# EDU_High-Speed-Design_DDR3.net
KiCad netlist of a schematic drawn in Altium Designer
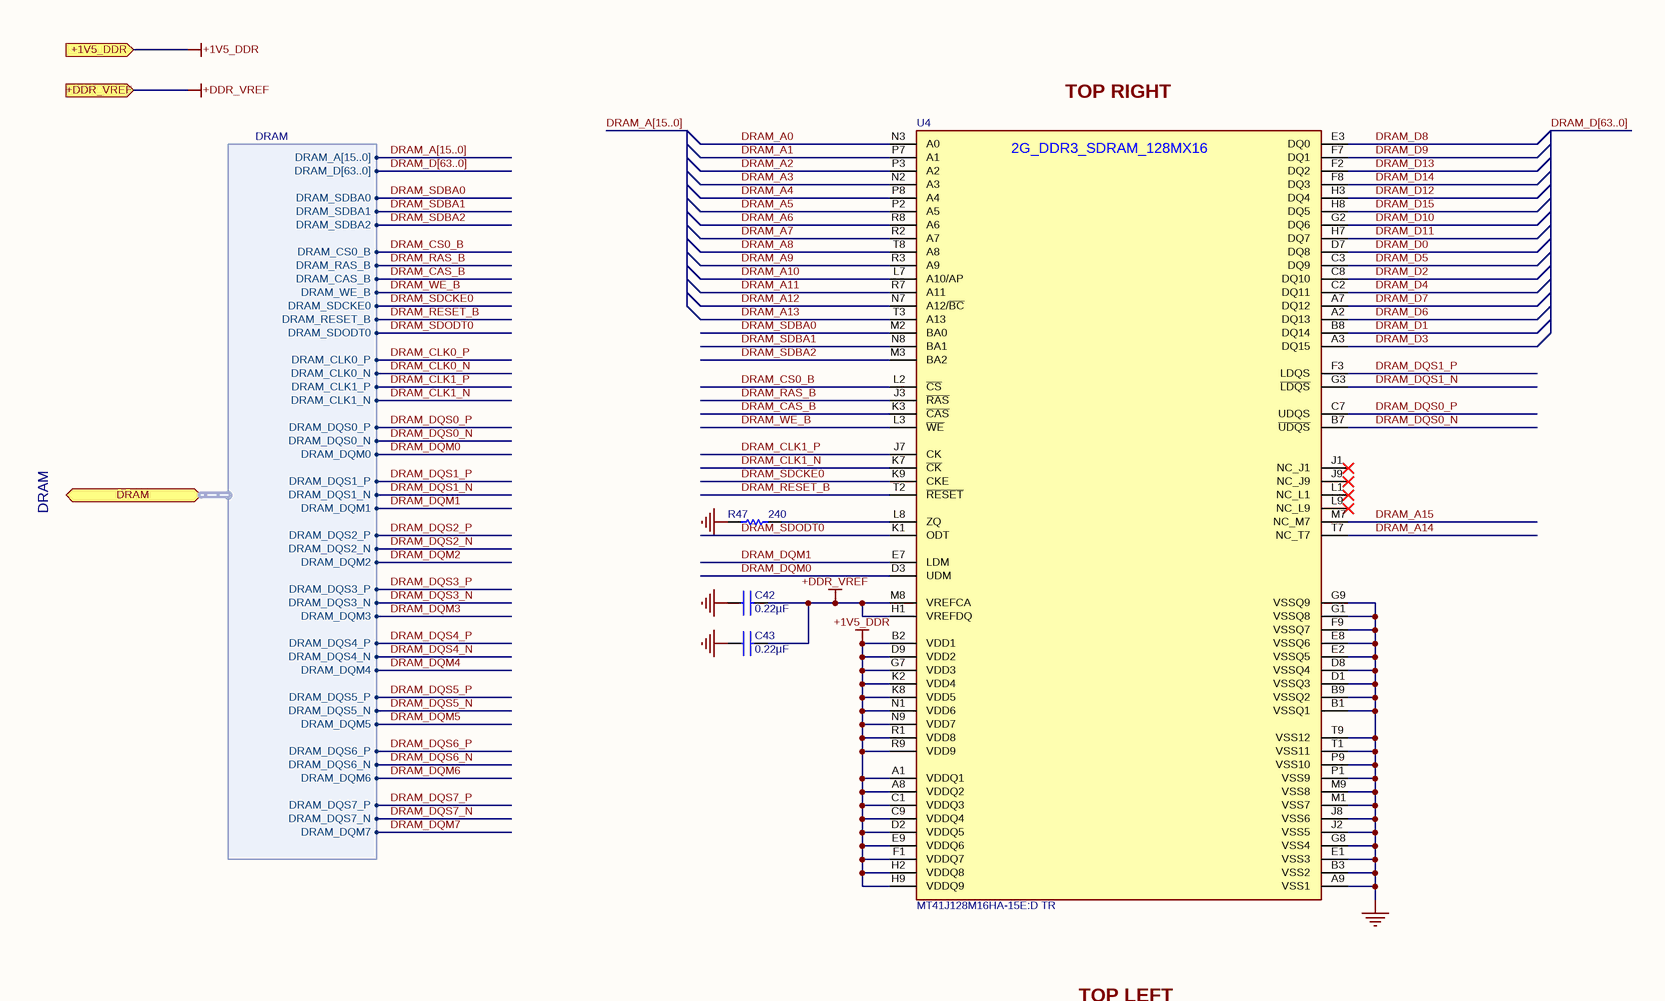
[diagram p0: EDU_High-Speed-Design_DDR3.SchDoc, top left]
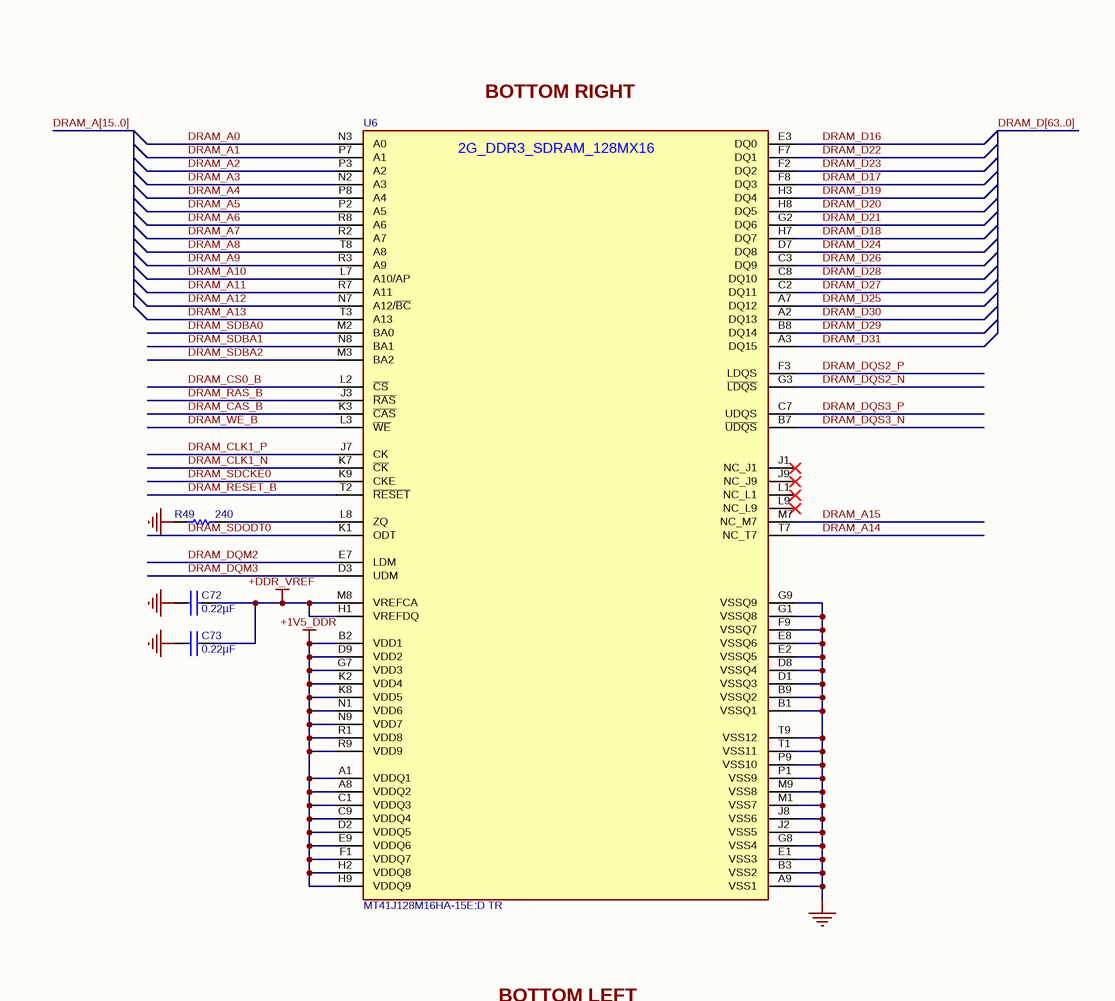
[diagram p1: EDU_High-Speed-Design_DDR3.SchDoc, top right]
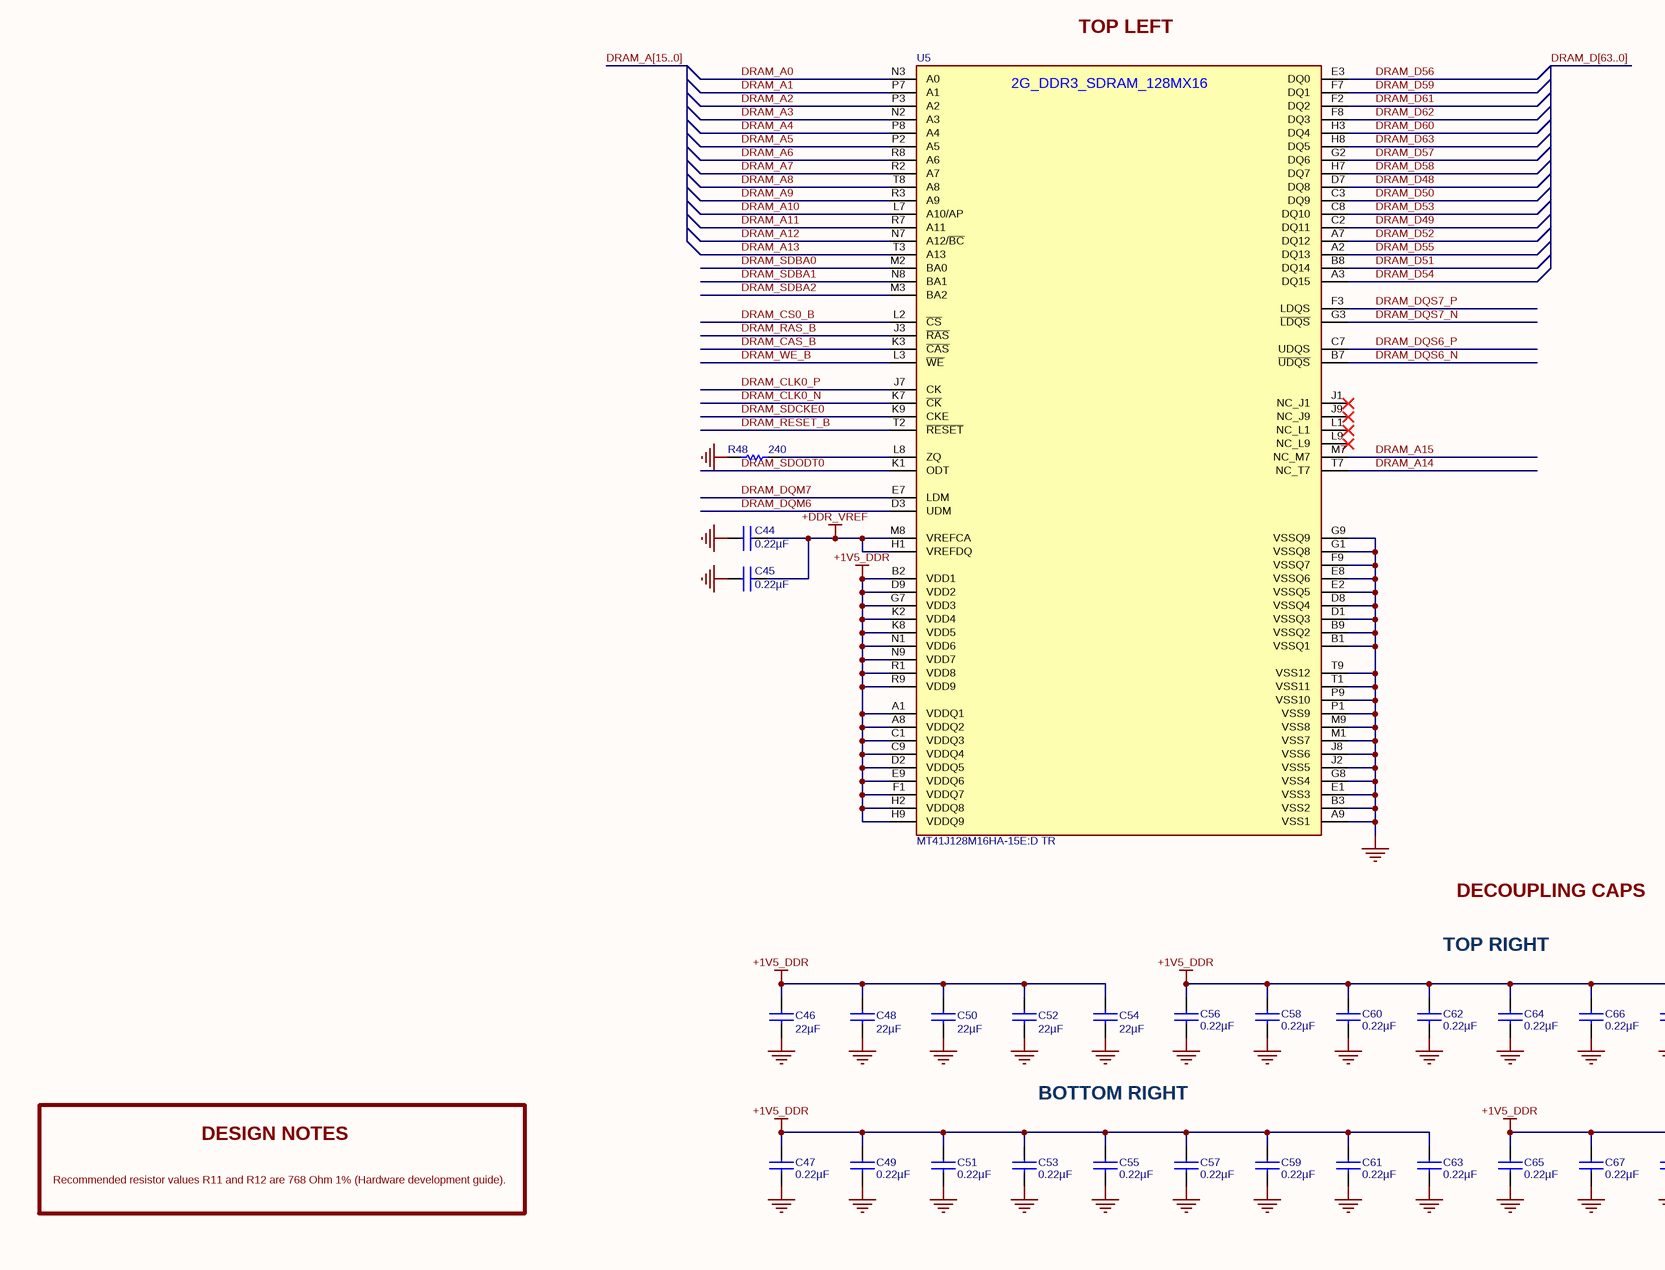
[diagram p2: EDU_High-Speed-Design_DDR3.SchDoc, bottom left]
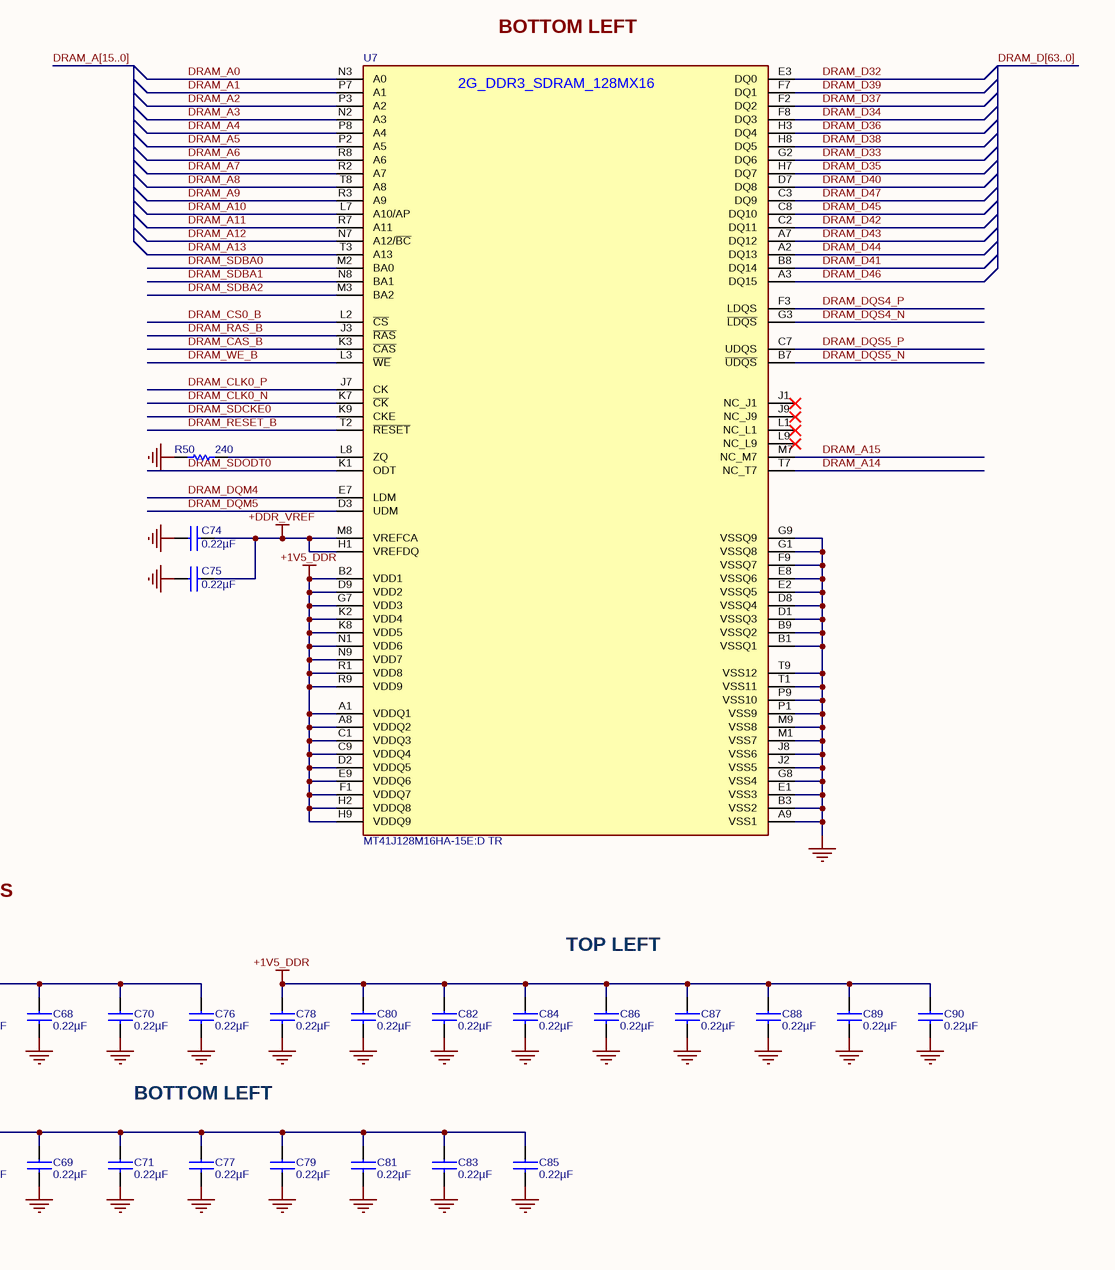
[diagram p3: EDU_High-Speed-Design_DDR3.SchDoc, bottom right]

(export (version "E")
  (design (tool "Eeschema 10.0.6"))
  (components
    (comp (ref "C42")
      (value "0.22µF")
      (footprint "C0402")
      (description "CAP CER .22UF 25V X5R 20% 0402")
      (fields (field (name "VOLTAGE") "25V"))
      (libsource (lib "EDU_High-Speed-Design") (part "C1005X5R1E224M"))
    )
    (comp (ref "C43")
      (value "0.22µF")
      (footprint "C0402")
      (description "CAP CER .22UF 25V X5R 20% 0402")
      (fields (field (name "VOLTAGE") "25V"))
      (libsource (lib "EDU_High-Speed-Design") (part "C1005X5R1E224M"))
    )
    (comp (ref "C44")
      (value "0.22µF")
      (footprint "C0402")
      (description "CAP CER .22UF 25V X5R 20% 0402")
      (fields (field (name "VOLTAGE") "25V"))
      (libsource (lib "EDU_High-Speed-Design") (part "C1005X5R1E224M"))
    )
    (comp (ref "C45")
      (value "0.22µF")
      (footprint "C0402")
      (description "CAP CER .22UF 25V X5R 20% 0402")
      (fields (field (name "VOLTAGE") "25V"))
      (libsource (lib "EDU_High-Speed-Design") (part "C1005X5R1E224M"))
    )
    (comp (ref "C46")
      (value "22µF")
      (footprint "C0603")
      (description "CAP CER 22UF 4V 20% X5R 0603")
      (fields (field (name "VOLTAGE") "4V"))
      (libsource (lib "EDU_High-Speed-Design") (part "GRM188R60G226MEA0L"))
    )
    (comp (ref "C47")
      (value "0.22µF")
      (footprint "C0402")
      (description "CAP CER .22UF 25V X5R 20% 0402")
      (fields (field (name "VOLTAGE") "25V"))
      (libsource (lib "EDU_High-Speed-Design") (part "C1005X5R1E224M"))
    )
    (comp (ref "C48")
      (value "22µF")
      (footprint "C0603")
      (description "CAP CER 22UF 4V 20% X5R 0603")
      (fields (field (name "VOLTAGE") "4V"))
      (libsource (lib "EDU_High-Speed-Design") (part "GRM188R60G226MEA0L"))
    )
    (comp (ref "C49")
      (value "0.22µF")
      (footprint "C0402")
      (description "CAP CER .22UF 25V X5R 20% 0402")
      (fields (field (name "VOLTAGE") "25V"))
      (libsource (lib "EDU_High-Speed-Design") (part "C1005X5R1E224M"))
    )
    (comp (ref "C50")
      (value "22µF")
      (footprint "C0603")
      (description "CAP CER 22UF 4V 20% X5R 0603")
      (fields (field (name "VOLTAGE") "4V"))
      (libsource (lib "EDU_High-Speed-Design") (part "GRM188R60G226MEA0L"))
    )
    (comp (ref "C51")
      (value "0.22µF")
      (footprint "C0402")
      (description "CAP CER .22UF 25V X5R 20% 0402")
      (fields (field (name "VOLTAGE") "25V"))
      (libsource (lib "EDU_High-Speed-Design") (part "C1005X5R1E224M"))
    )
    (comp (ref "C52")
      (value "22µF")
      (footprint "C0603")
      (description "CAP CER 22UF 4V 20% X5R 0603")
      (fields (field (name "VOLTAGE") "4V"))
      (libsource (lib "EDU_High-Speed-Design") (part "GRM188R60G226MEA0L"))
    )
    (comp (ref "C53")
      (value "0.22µF")
      (footprint "C0402")
      (description "CAP CER .22UF 25V X5R 20% 0402")
      (fields (field (name "VOLTAGE") "25V"))
      (libsource (lib "EDU_High-Speed-Design") (part "C1005X5R1E224M"))
    )
    (comp (ref "C54")
      (value "22µF")
      (footprint "C0603")
      (description "CAP CER 22UF 4V 20% X5R 0603")
      (fields (field (name "VOLTAGE") "4V"))
      (libsource (lib "EDU_High-Speed-Design") (part "GRM188R60G226MEA0L"))
    )
    (comp (ref "C55")
      (value "0.22µF")
      (footprint "C0402")
      (description "CAP CER .22UF 25V X5R 20% 0402")
      (fields (field (name "VOLTAGE") "25V"))
      (libsource (lib "EDU_High-Speed-Design") (part "C1005X5R1E224M"))
    )
    (comp (ref "C56")
      (value "0.22µF")
      (footprint "C0402")
      (description "CAP CER .22UF 25V X5R 20% 0402")
      (fields (field (name "VOLTAGE") "25V"))
      (libsource (lib "EDU_High-Speed-Design") (part "C1005X5R1E224M"))
    )
    (comp (ref "C57")
      (value "0.22µF")
      (footprint "C0402")
      (description "CAP CER .22UF 25V X5R 20% 0402")
      (fields (field (name "VOLTAGE") "25V"))
      (libsource (lib "EDU_High-Speed-Design") (part "C1005X5R1E224M"))
    )
    (comp (ref "C58")
      (value "0.22µF")
      (footprint "C0402")
      (description "CAP CER .22UF 25V X5R 20% 0402")
      (fields (field (name "VOLTAGE") "25V"))
      (libsource (lib "EDU_High-Speed-Design") (part "C1005X5R1E224M"))
    )
    (comp (ref "C59")
      (value "0.22µF")
      (footprint "C0402")
      (description "CAP CER .22UF 25V X5R 20% 0402")
      (fields (field (name "VOLTAGE") "25V"))
      (libsource (lib "EDU_High-Speed-Design") (part "C1005X5R1E224M"))
    )
    (comp (ref "C60")
      (value "0.22µF")
      (footprint "C0402")
      (description "CAP CER .22UF 25V X5R 20% 0402")
      (fields (field (name "VOLTAGE") "25V"))
      (libsource (lib "EDU_High-Speed-Design") (part "C1005X5R1E224M"))
    )
    (comp (ref "C61")
      (value "0.22µF")
      (footprint "C0402")
      (description "CAP CER .22UF 25V X5R 20% 0402")
      (fields (field (name "VOLTAGE") "25V"))
      (libsource (lib "EDU_High-Speed-Design") (part "C1005X5R1E224M"))
    )
    (comp (ref "C62")
      (value "0.22µF")
      (footprint "C0402")
      (description "CAP CER .22UF 25V X5R 20% 0402")
      (fields (field (name "VOLTAGE") "25V"))
      (libsource (lib "EDU_High-Speed-Design") (part "C1005X5R1E224M"))
    )
    (comp (ref "C63")
      (value "0.22µF")
      (footprint "C0402")
      (description "CAP CER .22UF 25V X5R 20% 0402")
      (fields (field (name "VOLTAGE") "25V"))
      (libsource (lib "EDU_High-Speed-Design") (part "C1005X5R1E224M"))
    )
    (comp (ref "C64")
      (value "0.22µF")
      (footprint "C0402")
      (description "CAP CER .22UF 25V X5R 20% 0402")
      (fields (field (name "VOLTAGE") "25V"))
      (libsource (lib "EDU_High-Speed-Design") (part "C1005X5R1E224M"))
    )
    (comp (ref "C65")
      (value "0.22µF")
      (footprint "C0402")
      (description "CAP CER .22UF 25V X5R 20% 0402")
      (fields (field (name "VOLTAGE") "25V"))
      (libsource (lib "EDU_High-Speed-Design") (part "C1005X5R1E224M"))
    )
    (comp (ref "C66")
      (value "0.22µF")
      (footprint "C0402")
      (description "CAP CER .22UF 25V X5R 20% 0402")
      (fields (field (name "VOLTAGE") "25V"))
      (libsource (lib "EDU_High-Speed-Design") (part "C1005X5R1E224M"))
    )
    (comp (ref "C67")
      (value "0.22µF")
      (footprint "C0402")
      (description "CAP CER .22UF 25V X5R 20% 0402")
      (fields (field (name "VOLTAGE") "25V"))
      (libsource (lib "EDU_High-Speed-Design") (part "C1005X5R1E224M"))
    )
    (comp (ref "C68")
      (value "0.22µF")
      (footprint "C0402")
      (description "CAP CER .22UF 25V X5R 20% 0402")
      (fields (field (name "VOLTAGE") "25V"))
      (libsource (lib "EDU_High-Speed-Design") (part "C1005X5R1E224M"))
    )
    (comp (ref "C69")
      (value "0.22µF")
      (footprint "C0402")
      (description "CAP CER .22UF 25V X5R 20% 0402")
      (fields (field (name "VOLTAGE") "25V"))
      (libsource (lib "EDU_High-Speed-Design") (part "C1005X5R1E224M"))
    )
    (comp (ref "C70")
      (value "0.22µF")
      (footprint "C0402")
      (description "CAP CER .22UF 25V X5R 20% 0402")
      (fields (field (name "VOLTAGE") "25V"))
      (libsource (lib "EDU_High-Speed-Design") (part "C1005X5R1E224M"))
    )
    (comp (ref "C71")
      (value "0.22µF")
      (footprint "C0402")
      (description "CAP CER .22UF 25V X5R 20% 0402")
      (fields (field (name "VOLTAGE") "25V"))
      (libsource (lib "EDU_High-Speed-Design") (part "C1005X5R1E224M"))
    )
    (comp (ref "C72")
      (value "0.22µF")
      (footprint "C0402")
      (description "CAP CER .22UF 25V X5R 20% 0402")
      (fields (field (name "VOLTAGE") "25V"))
      (libsource (lib "EDU_High-Speed-Design") (part "C1005X5R1E224M"))
    )
    (comp (ref "C73")
      (value "0.22µF")
      (footprint "C0402")
      (description "CAP CER .22UF 25V X5R 20% 0402")
      (fields (field (name "VOLTAGE") "25V"))
      (libsource (lib "EDU_High-Speed-Design") (part "C1005X5R1E224M"))
    )
    (comp (ref "C74")
      (value "0.22µF")
      (footprint "C0402")
      (description "CAP CER .22UF 25V X5R 20% 0402")
      (fields (field (name "VOLTAGE") "25V"))
      (libsource (lib "EDU_High-Speed-Design") (part "C1005X5R1E224M"))
    )
    (comp (ref "C75")
      (value "0.22µF")
      (footprint "C0402")
      (description "CAP CER .22UF 25V X5R 20% 0402")
      (fields (field (name "VOLTAGE") "25V"))
      (libsource (lib "EDU_High-Speed-Design") (part "C1005X5R1E224M"))
    )
    (comp (ref "C76")
      (value "0.22µF")
      (footprint "C0402")
      (description "CAP CER .22UF 25V X5R 20% 0402")
      (fields (field (name "VOLTAGE") "25V"))
      (libsource (lib "EDU_High-Speed-Design") (part "C1005X5R1E224M"))
    )
    (comp (ref "C77")
      (value "0.22µF")
      (footprint "C0402")
      (description "CAP CER .22UF 25V X5R 20% 0402")
      (fields (field (name "VOLTAGE") "25V"))
      (libsource (lib "EDU_High-Speed-Design") (part "C1005X5R1E224M"))
    )
    (comp (ref "C78")
      (value "0.22µF")
      (footprint "C0402")
      (description "CAP CER .22UF 25V X5R 20% 0402")
      (fields (field (name "VOLTAGE") "25V"))
      (libsource (lib "EDU_High-Speed-Design") (part "C1005X5R1E224M"))
    )
    (comp (ref "C79")
      (value "0.22µF")
      (footprint "C0402")
      (description "CAP CER .22UF 25V X5R 20% 0402")
      (fields (field (name "VOLTAGE") "25V"))
      (libsource (lib "EDU_High-Speed-Design") (part "C1005X5R1E224M"))
    )
    (comp (ref "C80")
      (value "0.22µF")
      (footprint "C0402")
      (description "CAP CER .22UF 25V X5R 20% 0402")
      (fields (field (name "VOLTAGE") "25V"))
      (libsource (lib "EDU_High-Speed-Design") (part "C1005X5R1E224M"))
    )
    (comp (ref "C81")
      (value "0.22µF")
      (footprint "C0402")
      (description "CAP CER .22UF 25V X5R 20% 0402")
      (fields (field (name "VOLTAGE") "25V"))
      (libsource (lib "EDU_High-Speed-Design") (part "C1005X5R1E224M"))
    )
    (comp (ref "C82")
      (value "0.22µF")
      (footprint "C0402")
      (description "CAP CER .22UF 25V X5R 20% 0402")
      (fields (field (name "VOLTAGE") "25V"))
      (libsource (lib "EDU_High-Speed-Design") (part "C1005X5R1E224M"))
    )
    (comp (ref "C83")
      (value "0.22µF")
      (footprint "C0402")
      (description "CAP CER .22UF 25V X5R 20% 0402")
      (fields (field (name "VOLTAGE") "25V"))
      (libsource (lib "EDU_High-Speed-Design") (part "C1005X5R1E224M"))
    )
    (comp (ref "C84")
      (value "0.22µF")
      (footprint "C0402")
      (description "CAP CER .22UF 25V X5R 20% 0402")
      (fields (field (name "VOLTAGE") "25V"))
      (libsource (lib "EDU_High-Speed-Design") (part "C1005X5R1E224M"))
    )
    (comp (ref "C85")
      (value "0.22µF")
      (footprint "C0402")
      (description "CAP CER .22UF 25V X5R 20% 0402")
      (fields (field (name "VOLTAGE") "25V"))
      (libsource (lib "EDU_High-Speed-Design") (part "C1005X5R1E224M"))
    )
    (comp (ref "C86")
      (value "0.22µF")
      (footprint "C0402")
      (description "CAP CER .22UF 25V X5R 20% 0402")
      (fields (field (name "VOLTAGE") "25V"))
      (libsource (lib "EDU_High-Speed-Design") (part "C1005X5R1E224M"))
    )
    (comp (ref "C87")
      (value "0.22µF")
      (footprint "C0402")
      (description "CAP CER .22UF 25V X5R 20% 0402")
      (fields (field (name "VOLTAGE") "25V"))
      (libsource (lib "EDU_High-Speed-Design") (part "C1005X5R1E224M"))
    )
    (comp (ref "C88")
      (value "0.22µF")
      (footprint "C0402")
      (description "CAP CER .22UF 25V X5R 20% 0402")
      (fields (field (name "VOLTAGE") "25V"))
      (libsource (lib "EDU_High-Speed-Design") (part "C1005X5R1E224M"))
    )
    (comp (ref "C89")
      (value "0.22µF")
      (footprint "C0402")
      (description "CAP CER .22UF 25V X5R 20% 0402")
      (fields (field (name "VOLTAGE") "25V"))
      (libsource (lib "EDU_High-Speed-Design") (part "C1005X5R1E224M"))
    )
    (comp (ref "C90")
      (value "0.22µF")
      (footprint "C0402")
      (description "CAP CER .22UF 25V X5R 20% 0402")
      (fields (field (name "VOLTAGE") "25V"))
      (libsource (lib "EDU_High-Speed-Design") (part "C1005X5R1E224M"))
    )
    (comp (ref "R47")
      (value "240")
      (footprint "R0402")
      (description "RES TF 240 OHM 1% 0.0625W 0402")
      (libsource (lib "EDU_High-Speed-Design") (part "RMCF0402FT240R"))
    )
    (comp (ref "R48")
      (value "240")
      (footprint "R0402")
      (description "RES TF 240 OHM 1% 0.0625W 0402")
      (libsource (lib "EDU_High-Speed-Design") (part "RMCF0402FT240R"))
    )
    (comp (ref "R49")
      (value "240")
      (footprint "R0402")
      (description "RES TF 240 OHM 1% 0.0625W 0402")
      (libsource (lib "EDU_High-Speed-Design") (part "RMCF0402FT240R"))
    )
    (comp (ref "R50")
      (value "240")
      (footprint "R0402")
      (description "RES TF 240 OHM 1% 0.0625W 0402")
      (libsource (lib "EDU_High-Speed-Design") (part "RMCF0402FT240R"))
    )
    (comp (ref "U4")
      (value "MT41J128M16HA-15E:D TR")
      (footprint "MT41J128M16HA-15E:D TR")
      (description "IC DDR3 SDRAM 2GBIT 667MHZ 96BGA")
      (libsource (lib "EDU_High-Speed-Design") (part "MT41J128M16HA-15E{colon}D TR"))
    )
    (comp (ref "U5")
      (value "MT41J128M16HA-15E:D TR")
      (footprint "MT41J128M16HA-15E:D TR")
      (description "IC DDR3 SDRAM 2GBIT 667MHZ 96BGA")
      (libsource (lib "EDU_High-Speed-Design") (part "MT41J128M16HA-15E{colon}D TR"))
    )
    (comp (ref "U6")
      (value "MT41J128M16HA-15E:D TR")
      (footprint "MT41J128M16HA-15E:D TR")
      (description "IC DDR3 SDRAM 2GBIT 667MHZ 96BGA")
      (libsource (lib "EDU_High-Speed-Design") (part "MT41J128M16HA-15E{colon}D TR"))
    )
    (comp (ref "U7")
      (value "MT41J128M16HA-15E:D TR")
      (footprint "MT41J128M16HA-15E:D TR")
      (description "IC DDR3 SDRAM 2GBIT 667MHZ 96BGA")
      (libsource (lib "EDU_High-Speed-Design") (part "MT41J128M16HA-15E{colon}D TR"))
    )
  )
  (nets
    (net (code "2") (name "+1V5_DDR") (class "Default")
      (node (ref "C46") (pin "1") (pinfunction "1_1") (pintype "passive"))
      (node (ref "C47") (pin "1") (pinfunction "1_1") (pintype "passive"))
      (node (ref "C48") (pin "1") (pinfunction "1_1") (pintype "passive"))
      (node (ref "C49") (pin "1") (pinfunction "1_1") (pintype "passive"))
      (node (ref "C50") (pin "1") (pinfunction "1_1") (pintype "passive"))
      (node (ref "C51") (pin "1") (pinfunction "1_1") (pintype "passive"))
      (node (ref "C52") (pin "1") (pinfunction "1_1") (pintype "passive"))
      (node (ref "C53") (pin "1") (pinfunction "1_1") (pintype "passive"))
      (node (ref "C54") (pin "1") (pinfunction "1_1") (pintype "passive"))
      (node (ref "C55") (pin "1") (pinfunction "1_1") (pintype "passive"))
      (node (ref "C56") (pin "1") (pinfunction "1_1") (pintype "passive"))
      (node (ref "C57") (pin "1") (pinfunction "1_1") (pintype "passive"))
      (node (ref "C58") (pin "1") (pinfunction "1_1") (pintype "passive"))
      (node (ref "C59") (pin "1") (pinfunction "1_1") (pintype "passive"))
      (node (ref "C60") (pin "1") (pinfunction "1_1") (pintype "passive"))
      (node (ref "C61") (pin "1") (pinfunction "1_1") (pintype "passive"))
      (node (ref "C62") (pin "1") (pinfunction "1_1") (pintype "passive"))
      (node (ref "C63") (pin "1") (pinfunction "1_1") (pintype "passive"))
      (node (ref "C64") (pin "1") (pinfunction "1_1") (pintype "passive"))
      (node (ref "C65") (pin "1") (pinfunction "1_1") (pintype "passive"))
      (node (ref "C66") (pin "1") (pinfunction "1_1") (pintype "passive"))
      (node (ref "C67") (pin "1") (pinfunction "1_1") (pintype "passive"))
      (node (ref "C68") (pin "1") (pinfunction "1_1") (pintype "passive"))
      (node (ref "C69") (pin "1") (pinfunction "1_1") (pintype "passive"))
      (node (ref "C70") (pin "1") (pinfunction "1_1") (pintype "passive"))
      (node (ref "C71") (pin "1") (pinfunction "1_1") (pintype "passive"))
      (node (ref "C76") (pin "1") (pinfunction "1_1") (pintype "passive"))
      (node (ref "C77") (pin "1") (pinfunction "1_1") (pintype "passive"))
      (node (ref "C78") (pin "1") (pinfunction "1_1") (pintype "passive"))
      (node (ref "C79") (pin "1") (pinfunction "1_1") (pintype "passive"))
      (node (ref "C80") (pin "1") (pinfunction "1_1") (pintype "passive"))
      (node (ref "C81") (pin "1") (pinfunction "1_1") (pintype "passive"))
      (node (ref "C82") (pin "1") (pinfunction "1_1") (pintype "passive"))
      (node (ref "C83") (pin "1") (pinfunction "1_1") (pintype "passive"))
      (node (ref "C84") (pin "1") (pinfunction "1_1") (pintype "passive"))
      (node (ref "C85") (pin "1") (pinfunction "1_1") (pintype "passive"))
      (node (ref "C86") (pin "1") (pinfunction "1_1") (pintype "passive"))
      (node (ref "C87") (pin "1") (pinfunction "1_1") (pintype "passive"))
      (node (ref "C88") (pin "1") (pinfunction "1_1") (pintype "passive"))
      (node (ref "C89") (pin "1") (pinfunction "1_1") (pintype "passive"))
      (node (ref "C90") (pin "1") (pinfunction "1_1") (pintype "passive"))
      (node (ref "U4") (pin "A1") (pinfunction "VDDQ1_A1") (pintype "passive"))
      (node (ref "U4") (pin "A8") (pinfunction "VDDQ2_A8") (pintype "passive"))
      (node (ref "U4") (pin "B2") (pinfunction "VDD1_B2") (pintype "passive"))
      (node (ref "U4") (pin "C1") (pinfunction "VDDQ3_C1") (pintype "passive"))
      (node (ref "U4") (pin "C9") (pinfunction "VDDQ4_C9") (pintype "passive"))
      (node (ref "U4") (pin "D2") (pinfunction "VDDQ5_D2") (pintype "passive"))
      (node (ref "U4") (pin "D9") (pinfunction "VDD2_D9") (pintype "passive"))
      (node (ref "U4") (pin "E9") (pinfunction "VDDQ6_E9") (pintype "passive"))
      (node (ref "U4") (pin "F1") (pinfunction "VDDQ7_F1") (pintype "passive"))
      (node (ref "U4") (pin "G7") (pinfunction "VDD3_G7") (pintype "passive"))
      (node (ref "U4") (pin "H2") (pinfunction "VDDQ8_H2") (pintype "passive"))
      (node (ref "U4") (pin "H9") (pinfunction "VDDQ9_H9") (pintype "passive"))
      (node (ref "U4") (pin "K2") (pinfunction "VDD4_K2") (pintype "passive"))
      (node (ref "U4") (pin "K8") (pinfunction "VDD5_K8") (pintype "passive"))
      (node (ref "U4") (pin "N1") (pinfunction "VDD6_N1") (pintype "passive"))
      (node (ref "U4") (pin "N9") (pinfunction "VDD7_N9") (pintype "passive"))
      (node (ref "U4") (pin "R1") (pinfunction "VDD8_R1") (pintype "passive"))
      (node (ref "U4") (pin "R9") (pinfunction "VDD9_R9") (pintype "passive"))
      (node (ref "U5") (pin "A1") (pinfunction "VDDQ1_A1") (pintype "passive"))
      (node (ref "U5") (pin "A8") (pinfunction "VDDQ2_A8") (pintype "passive"))
      (node (ref "U5") (pin "B2") (pinfunction "VDD1_B2") (pintype "passive"))
      (node (ref "U5") (pin "C1") (pinfunction "VDDQ3_C1") (pintype "passive"))
      (node (ref "U5") (pin "C9") (pinfunction "VDDQ4_C9") (pintype "passive"))
      (node (ref "U5") (pin "D2") (pinfunction "VDDQ5_D2") (pintype "passive"))
      (node (ref "U5") (pin "D9") (pinfunction "VDD2_D9") (pintype "passive"))
      (node (ref "U5") (pin "E9") (pinfunction "VDDQ6_E9") (pintype "passive"))
      (node (ref "U5") (pin "F1") (pinfunction "VDDQ7_F1") (pintype "passive"))
      (node (ref "U5") (pin "G7") (pinfunction "VDD3_G7") (pintype "passive"))
      (node (ref "U5") (pin "H2") (pinfunction "VDDQ8_H2") (pintype "passive"))
      (node (ref "U5") (pin "H9") (pinfunction "VDDQ9_H9") (pintype "passive"))
      (node (ref "U5") (pin "K2") (pinfunction "VDD4_K2") (pintype "passive"))
      (node (ref "U5") (pin "K8") (pinfunction "VDD5_K8") (pintype "passive"))
      (node (ref "U5") (pin "N1") (pinfunction "VDD6_N1") (pintype "passive"))
      (node (ref "U5") (pin "N9") (pinfunction "VDD7_N9") (pintype "passive"))
      (node (ref "U5") (pin "R1") (pinfunction "VDD8_R1") (pintype "passive"))
      (node (ref "U5") (pin "R9") (pinfunction "VDD9_R9") (pintype "passive"))
      (node (ref "U6") (pin "A1") (pinfunction "VDDQ1_A1") (pintype "passive"))
      (node (ref "U6") (pin "A8") (pinfunction "VDDQ2_A8") (pintype "passive"))
      (node (ref "U6") (pin "B2") (pinfunction "VDD1_B2") (pintype "passive"))
      (node (ref "U6") (pin "C1") (pinfunction "VDDQ3_C1") (pintype "passive"))
      (node (ref "U6") (pin "C9") (pinfunction "VDDQ4_C9") (pintype "passive"))
      (node (ref "U6") (pin "D2") (pinfunction "VDDQ5_D2") (pintype "passive"))
      (node (ref "U6") (pin "D9") (pinfunction "VDD2_D9") (pintype "passive"))
      (node (ref "U6") (pin "E9") (pinfunction "VDDQ6_E9") (pintype "passive"))
      (node (ref "U6") (pin "F1") (pinfunction "VDDQ7_F1") (pintype "passive"))
      (node (ref "U6") (pin "G7") (pinfunction "VDD3_G7") (pintype "passive"))
      (node (ref "U6") (pin "H2") (pinfunction "VDDQ8_H2") (pintype "passive"))
      (node (ref "U6") (pin "H9") (pinfunction "VDDQ9_H9") (pintype "passive"))
      (node (ref "U6") (pin "K2") (pinfunction "VDD4_K2") (pintype "passive"))
      (node (ref "U6") (pin "K8") (pinfunction "VDD5_K8") (pintype "passive"))
      (node (ref "U6") (pin "N1") (pinfunction "VDD6_N1") (pintype "passive"))
      (node (ref "U6") (pin "N9") (pinfunction "VDD7_N9") (pintype "passive"))
      (node (ref "U6") (pin "R1") (pinfunction "VDD8_R1") (pintype "passive"))
      (node (ref "U6") (pin "R9") (pinfunction "VDD9_R9") (pintype "passive"))
      (node (ref "U7") (pin "A1") (pinfunction "VDDQ1_A1") (pintype "passive"))
      (node (ref "U7") (pin "A8") (pinfunction "VDDQ2_A8") (pintype "passive"))
      (node (ref "U7") (pin "B2") (pinfunction "VDD1_B2") (pintype "passive"))
      (node (ref "U7") (pin "C1") (pinfunction "VDDQ3_C1") (pintype "passive"))
      (node (ref "U7") (pin "C9") (pinfunction "VDDQ4_C9") (pintype "passive"))
      (node (ref "U7") (pin "D2") (pinfunction "VDDQ5_D2") (pintype "passive"))
      (node (ref "U7") (pin "D9") (pinfunction "VDD2_D9") (pintype "passive"))
      (node (ref "U7") (pin "E9") (pinfunction "VDDQ6_E9") (pintype "passive"))
      (node (ref "U7") (pin "F1") (pinfunction "VDDQ7_F1") (pintype "passive"))
      (node (ref "U7") (pin "G7") (pinfunction "VDD3_G7") (pintype "passive"))
      (node (ref "U7") (pin "H2") (pinfunction "VDDQ8_H2") (pintype "passive"))
      (node (ref "U7") (pin "H9") (pinfunction "VDDQ9_H9") (pintype "passive"))
      (node (ref "U7") (pin "K2") (pinfunction "VDD4_K2") (pintype "passive"))
      (node (ref "U7") (pin "K8") (pinfunction "VDD5_K8") (pintype "passive"))
      (node (ref "U7") (pin "N1") (pinfunction "VDD6_N1") (pintype "passive"))
      (node (ref "U7") (pin "N9") (pinfunction "VDD7_N9") (pintype "passive"))
      (node (ref "U7") (pin "R1") (pinfunction "VDD8_R1") (pintype "passive"))
      (node (ref "U7") (pin "R9") (pinfunction "VDD9_R9") (pintype "passive"))
    )
    (net (code "3") (name "+DDR_VREF") (class "Default")
      (node (ref "C42") (pin "2") (pinfunction "2_2") (pintype "passive"))
      (node (ref "C43") (pin "2") (pinfunction "2_2") (pintype "passive"))
      (node (ref "C44") (pin "2") (pinfunction "2_2") (pintype "passive"))
      (node (ref "C45") (pin "2") (pinfunction "2_2") (pintype "passive"))
      (node (ref "C72") (pin "2") (pinfunction "2_2") (pintype "passive"))
      (node (ref "C73") (pin "2") (pinfunction "2_2") (pintype "passive"))
      (node (ref "C74") (pin "2") (pinfunction "2_2") (pintype "passive"))
      (node (ref "C75") (pin "2") (pinfunction "2_2") (pintype "passive"))
      (node (ref "U4") (pin "H1") (pinfunction "VREFDQ_H1") (pintype "passive"))
      (node (ref "U4") (pin "M8") (pinfunction "VREFCA_M8") (pintype "passive"))
      (node (ref "U5") (pin "H1") (pinfunction "VREFDQ_H1") (pintype "passive"))
      (node (ref "U5") (pin "M8") (pinfunction "VREFCA_M8") (pintype "passive"))
      (node (ref "U6") (pin "H1") (pinfunction "VREFDQ_H1") (pintype "passive"))
      (node (ref "U6") (pin "M8") (pinfunction "VREFCA_M8") (pintype "passive"))
      (node (ref "U7") (pin "H1") (pinfunction "VREFDQ_H1") (pintype "passive"))
      (node (ref "U7") (pin "M8") (pinfunction "VREFCA_M8") (pintype "passive"))
    )
    (net (code "4") (name "/DRAM_A0") (class "Default")
      (node (ref "U4") (pin "N3") (pinfunction "A0_N3") (pintype "passive"))
      (node (ref "U5") (pin "N3") (pinfunction "A0_N3") (pintype "passive"))
      (node (ref "U6") (pin "N3") (pinfunction "A0_N3") (pintype "passive"))
      (node (ref "U7") (pin "N3") (pinfunction "A0_N3") (pintype "passive"))
    )
    (net (code "5") (name "/DRAM_A1") (class "Default")
      (node (ref "U4") (pin "P7") (pinfunction "A1_P7") (pintype "passive"))
      (node (ref "U5") (pin "P7") (pinfunction "A1_P7") (pintype "passive"))
      (node (ref "U6") (pin "P7") (pinfunction "A1_P7") (pintype "passive"))
      (node (ref "U7") (pin "P7") (pinfunction "A1_P7") (pintype "passive"))
    )
    (net (code "6") (name "/DRAM_A2") (class "Default")
      (node (ref "U4") (pin "P3") (pinfunction "A2_P3") (pintype "passive"))
      (node (ref "U5") (pin "P3") (pinfunction "A2_P3") (pintype "passive"))
      (node (ref "U6") (pin "P3") (pinfunction "A2_P3") (pintype "passive"))
      (node (ref "U7") (pin "P3") (pinfunction "A2_P3") (pintype "passive"))
    )
    (net (code "7") (name "/DRAM_A3") (class "Default")
      (node (ref "U4") (pin "N2") (pinfunction "A3_N2") (pintype "passive"))
      (node (ref "U5") (pin "N2") (pinfunction "A3_N2") (pintype "passive"))
      (node (ref "U6") (pin "N2") (pinfunction "A3_N2") (pintype "passive"))
      (node (ref "U7") (pin "N2") (pinfunction "A3_N2") (pintype "passive"))
    )
    (net (code "8") (name "/DRAM_A4") (class "Default")
      (node (ref "U4") (pin "P8") (pinfunction "A4_P8") (pintype "passive"))
      (node (ref "U5") (pin "P8") (pinfunction "A4_P8") (pintype "passive"))
      (node (ref "U6") (pin "P8") (pinfunction "A4_P8") (pintype "passive"))
      (node (ref "U7") (pin "P8") (pinfunction "A4_P8") (pintype "passive"))
    )
    (net (code "9") (name "/DRAM_A5") (class "Default")
      (node (ref "U4") (pin "P2") (pinfunction "A5_P2") (pintype "passive"))
      (node (ref "U5") (pin "P2") (pinfunction "A5_P2") (pintype "passive"))
      (node (ref "U6") (pin "P2") (pinfunction "A5_P2") (pintype "passive"))
      (node (ref "U7") (pin "P2") (pinfunction "A5_P2") (pintype "passive"))
    )
    (net (code "10") (name "/DRAM_A6") (class "Default")
      (node (ref "U4") (pin "R8") (pinfunction "A6_R8") (pintype "passive"))
      (node (ref "U5") (pin "R8") (pinfunction "A6_R8") (pintype "passive"))
      (node (ref "U6") (pin "R8") (pinfunction "A6_R8") (pintype "passive"))
      (node (ref "U7") (pin "R8") (pinfunction "A6_R8") (pintype "passive"))
    )
    (net (code "11") (name "/DRAM_A7") (class "Default")
      (node (ref "U4") (pin "R2") (pinfunction "A7_R2") (pintype "passive"))
      (node (ref "U5") (pin "R2") (pinfunction "A7_R2") (pintype "passive"))
      (node (ref "U6") (pin "R2") (pinfunction "A7_R2") (pintype "passive"))
      (node (ref "U7") (pin "R2") (pinfunction "A7_R2") (pintype "passive"))
    )
    (net (code "12") (name "/DRAM_A8") (class "Default")
      (node (ref "U4") (pin "T8") (pinfunction "A8_T8") (pintype "passive"))
      (node (ref "U5") (pin "T8") (pinfunction "A8_T8") (pintype "passive"))
      (node (ref "U6") (pin "T8") (pinfunction "A8_T8") (pintype "passive"))
      (node (ref "U7") (pin "T8") (pinfunction "A8_T8") (pintype "passive"))
    )
    (net (code "13") (name "/DRAM_A9") (class "Default")
      (node (ref "U4") (pin "R3") (pinfunction "A9_R3") (pintype "passive"))
      (node (ref "U5") (pin "R3") (pinfunction "A9_R3") (pintype "passive"))
      (node (ref "U6") (pin "R3") (pinfunction "A9_R3") (pintype "passive"))
      (node (ref "U7") (pin "R3") (pinfunction "A9_R3") (pintype "passive"))
    )
    (net (code "14") (name "/DRAM_A10") (class "Default")
      (node (ref "U4") (pin "L7") (pinfunction "A10/AP_L7") (pintype "passive"))
      (node (ref "U5") (pin "L7") (pinfunction "A10/AP_L7") (pintype "passive"))
      (node (ref "U6") (pin "L7") (pinfunction "A10/AP_L7") (pintype "passive"))
      (node (ref "U7") (pin "L7") (pinfunction "A10/AP_L7") (pintype "passive"))
    )
    (net (code "15") (name "/DRAM_A11") (class "Default")
      (node (ref "U4") (pin "R7") (pinfunction "A11_R7") (pintype "passive"))
      (node (ref "U5") (pin "R7") (pinfunction "A11_R7") (pintype "passive"))
      (node (ref "U6") (pin "R7") (pinfunction "A11_R7") (pintype "passive"))
      (node (ref "U7") (pin "R7") (pinfunction "A11_R7") (pintype "passive"))
    )
    (net (code "16") (name "/DRAM_A12") (class "Default")
      (node (ref "U4") (pin "N7") (pinfunction "A12/~{BC}_N7") (pintype "passive"))
      (node (ref "U5") (pin "N7") (pinfunction "A12/~{BC}_N7") (pintype "passive"))
      (node (ref "U6") (pin "N7") (pinfunction "A12/~{BC}_N7") (pintype "passive"))
      (node (ref "U7") (pin "N7") (pinfunction "A12/~{BC}_N7") (pintype "passive"))
    )
    (net (code "17") (name "/DRAM_A13") (class "Default")
      (node (ref "U4") (pin "T3") (pinfunction "A13_T3") (pintype "passive"))
      (node (ref "U5") (pin "T3") (pinfunction "A13_T3") (pintype "passive"))
      (node (ref "U6") (pin "T3") (pinfunction "A13_T3") (pintype "passive"))
      (node (ref "U7") (pin "T3") (pinfunction "A13_T3") (pintype "passive"))
    )
    (net (code "18") (name "/DRAM_A14") (class "Default")
      (node (ref "U4") (pin "T7") (pinfunction "NC_T7_T7") (pintype "passive"))
      (node (ref "U5") (pin "T7") (pinfunction "NC_T7_T7") (pintype "passive"))
      (node (ref "U6") (pin "T7") (pinfunction "NC_T7_T7") (pintype "passive"))
      (node (ref "U7") (pin "T7") (pinfunction "NC_T7_T7") (pintype "passive"))
    )
    (net (code "19") (name "/DRAM_A15") (class "Default")
      (node (ref "U4") (pin "M7") (pinfunction "NC_M7_M7") (pintype "passive"))
      (node (ref "U5") (pin "M7") (pinfunction "NC_M7_M7") (pintype "passive"))
      (node (ref "U6") (pin "M7") (pinfunction "NC_M7_M7") (pintype "passive"))
      (node (ref "U7") (pin "M7") (pinfunction "NC_M7_M7") (pintype "passive"))
    )
    (net (code "21") (name "/DRAM_CAS_B") (class "Default")
      (node (ref "U4") (pin "K3") (pinfunction "~{CAS}_K3") (pintype "passive"))
      (node (ref "U5") (pin "K3") (pinfunction "~{CAS}_K3") (pintype "passive"))
      (node (ref "U6") (pin "K3") (pinfunction "~{CAS}_K3") (pintype "passive"))
      (node (ref "U7") (pin "K3") (pinfunction "~{CAS}_K3") (pintype "passive"))
    )
    (net (code "22") (name "/DRAM_CLK0_N") (class "Default")
      (node (ref "U5") (pin "K7") (pinfunction "~{CK}_K7") (pintype "passive"))
      (node (ref "U7") (pin "K7") (pinfunction "~{CK}_K7") (pintype "passive"))
    )
    (net (code "23") (name "/DRAM_CLK0_P") (class "Default")
      (node (ref "U5") (pin "J7") (pinfunction "CK_J7") (pintype "passive"))
      (node (ref "U7") (pin "J7") (pinfunction "CK_J7") (pintype "passive"))
    )
    (net (code "24") (name "/DRAM_CLK1_N") (class "Default")
      (node (ref "U4") (pin "K7") (pinfunction "~{CK}_K7") (pintype "passive"))
      (node (ref "U6") (pin "K7") (pinfunction "~{CK}_K7") (pintype "passive"))
    )
    (net (code "25") (name "/DRAM_CLK1_P") (class "Default")
      (node (ref "U4") (pin "J7") (pinfunction "CK_J7") (pintype "passive"))
      (node (ref "U6") (pin "J7") (pinfunction "CK_J7") (pintype "passive"))
    )
    (net (code "26") (name "/DRAM_CS0_B") (class "Default")
      (node (ref "U4") (pin "L2") (pinfunction "~{CS}_L2") (pintype "passive"))
      (node (ref "U5") (pin "L2") (pinfunction "~{CS}_L2") (pintype "passive"))
      (node (ref "U6") (pin "L2") (pinfunction "~{CS}_L2") (pintype "passive"))
      (node (ref "U7") (pin "L2") (pinfunction "~{CS}_L2") (pintype "passive"))
    )
    (net (code "27") (name "/DRAM_D0") (class "Default")
      (node (ref "U4") (pin "D7") (pinfunction "DQ8_D7") (pintype "passive"))
    )
    (net (code "28") (name "/DRAM_D1") (class "Default")
      (node (ref "U4") (pin "B8") (pinfunction "DQ14_B8") (pintype "passive"))
    )
    (net (code "29") (name "/DRAM_D2") (class "Default")
      (node (ref "U4") (pin "C8") (pinfunction "DQ10_C8") (pintype "passive"))
    )
    (net (code "30") (name "/DRAM_D3") (class "Default")
      (node (ref "U4") (pin "A3") (pinfunction "DQ15_A3") (pintype "passive"))
    )
    (net (code "31") (name "/DRAM_D4") (class "Default")
      (node (ref "U4") (pin "C2") (pinfunction "DQ11_C2") (pintype "passive"))
    )
    (net (code "32") (name "/DRAM_D5") (class "Default")
      (node (ref "U4") (pin "C3") (pinfunction "DQ9_C3") (pintype "passive"))
    )
    (net (code "33") (name "/DRAM_D6") (class "Default")
      (node (ref "U4") (pin "A2") (pinfunction "DQ13_A2") (pintype "passive"))
    )
    (net (code "34") (name "/DRAM_D7") (class "Default")
      (node (ref "U4") (pin "A7") (pinfunction "DQ12_A7") (pintype "passive"))
    )
    (net (code "35") (name "/DRAM_D8") (class "Default")
      (node (ref "U4") (pin "E3") (pinfunction "DQ0_E3") (pintype "passive"))
    )
    (net (code "36") (name "/DRAM_D9") (class "Default")
      (node (ref "U4") (pin "F7") (pinfunction "DQ1_F7") (pintype "passive"))
    )
    (net (code "37") (name "/DRAM_D10") (class "Default")
      (node (ref "U4") (pin "G2") (pinfunction "DQ6_G2") (pintype "passive"))
    )
    (net (code "38") (name "/DRAM_D11") (class "Default")
      (node (ref "U4") (pin "H7") (pinfunction "DQ7_H7") (pintype "passive"))
    )
    (net (code "39") (name "/DRAM_D12") (class "Default")
      (node (ref "U4") (pin "H3") (pinfunction "DQ4_H3") (pintype "passive"))
    )
    (net (code "40") (name "/DRAM_D13") (class "Default")
      (node (ref "U4") (pin "F2") (pinfunction "DQ2_F2") (pintype "passive"))
    )
    (net (code "41") (name "/DRAM_D14") (class "Default")
      (node (ref "U4") (pin "F8") (pinfunction "DQ3_F8") (pintype "passive"))
    )
    (net (code "42") (name "/DRAM_D15") (class "Default")
      (node (ref "U4") (pin "H8") (pinfunction "DQ5_H8") (pintype "passive"))
    )
    (net (code "43") (name "/DRAM_D16") (class "Default")
      (node (ref "U6") (pin "E3") (pinfunction "DQ0_E3") (pintype "passive"))
    )
    (net (code "44") (name "/DRAM_D17") (class "Default")
      (node (ref "U6") (pin "F8") (pinfunction "DQ3_F8") (pintype "passive"))
    )
    (net (code "45") (name "/DRAM_D18") (class "Default")
      (node (ref "U6") (pin "H7") (pinfunction "DQ7_H7") (pintype "passive"))
    )
    (net (code "46") (name "/DRAM_D19") (class "Default")
      (node (ref "U6") (pin "H3") (pinfunction "DQ4_H3") (pintype "passive"))
    )
    (net (code "47") (name "/DRAM_D20") (class "Default")
      (node (ref "U6") (pin "H8") (pinfunction "DQ5_H8") (pintype "passive"))
    )
    (net (code "48") (name "/DRAM_D21") (class "Default")
      (node (ref "U6") (pin "G2") (pinfunction "DQ6_G2") (pintype "passive"))
    )
    (net (code "49") (name "/DRAM_D22") (class "Default")
      (node (ref "U6") (pin "F7") (pinfunction "DQ1_F7") (pintype "passive"))
    )
    (net (code "50") (name "/DRAM_D23") (class "Default")
      (node (ref "U6") (pin "F2") (pinfunction "DQ2_F2") (pintype "passive"))
    )
    (net (code "51") (name "/DRAM_D24") (class "Default")
      (node (ref "U6") (pin "D7") (pinfunction "DQ8_D7") (pintype "passive"))
    )
    (net (code "52") (name "/DRAM_D25") (class "Default")
      (node (ref "U6") (pin "A7") (pinfunction "DQ12_A7") (pintype "passive"))
    )
    (net (code "53") (name "/DRAM_D26") (class "Default")
      (node (ref "U6") (pin "C3") (pinfunction "DQ9_C3") (pintype "passive"))
    )
    (net (code "54") (name "/DRAM_D27") (class "Default")
      (node (ref "U6") (pin "C2") (pinfunction "DQ11_C2") (pintype "passive"))
    )
    (net (code "55") (name "/DRAM_D28") (class "Default")
      (node (ref "U6") (pin "C8") (pinfunction "DQ10_C8") (pintype "passive"))
    )
    (net (code "56") (name "/DRAM_D29") (class "Default")
      (node (ref "U6") (pin "B8") (pinfunction "DQ14_B8") (pintype "passive"))
    )
    (net (code "57") (name "/DRAM_D30") (class "Default")
      (node (ref "U6") (pin "A2") (pinfunction "DQ13_A2") (pintype "passive"))
    )
    (net (code "58") (name "/DRAM_D31") (class "Default")
      (node (ref "U6") (pin "A3") (pinfunction "DQ15_A3") (pintype "passive"))
    )
    (net (code "59") (name "/DRAM_D32") (class "Default")
      (node (ref "U7") (pin "E3") (pinfunction "DQ0_E3") (pintype "passive"))
    )
    (net (code "60") (name "/DRAM_D33") (class "Default")
      (node (ref "U7") (pin "G2") (pinfunction "DQ6_G2") (pintype "passive"))
    )
    (net (code "61") (name "/DRAM_D34") (class "Default")
      (node (ref "U7") (pin "F8") (pinfunction "DQ3_F8") (pintype "passive"))
    )
    (net (code "62") (name "/DRAM_D35") (class "Default")
      (node (ref "U7") (pin "H7") (pinfunction "DQ7_H7") (pintype "passive"))
    )
    (net (code "63") (name "/DRAM_D36") (class "Default")
      (node (ref "U7") (pin "H3") (pinfunction "DQ4_H3") (pintype "passive"))
    )
    (net (code "64") (name "/DRAM_D37") (class "Default")
      (node (ref "U7") (pin "F2") (pinfunction "DQ2_F2") (pintype "passive"))
    )
    (net (code "65") (name "/DRAM_D38") (class "Default")
      (node (ref "U7") (pin "H8") (pinfunction "DQ5_H8") (pintype "passive"))
    )
    (net (code "66") (name "/DRAM_D39") (class "Default")
      (node (ref "U7") (pin "F7") (pinfunction "DQ1_F7") (pintype "passive"))
    )
    (net (code "67") (name "/DRAM_D40") (class "Default")
      (node (ref "U7") (pin "D7") (pinfunction "DQ8_D7") (pintype "passive"))
    )
    (net (code "68") (name "/DRAM_D41") (class "Default")
      (node (ref "U7") (pin "B8") (pinfunction "DQ14_B8") (pintype "passive"))
    )
    (net (code "69") (name "/DRAM_D42") (class "Default")
      (node (ref "U7") (pin "C2") (pinfunction "DQ11_C2") (pintype "passive"))
    )
    (net (code "70") (name "/DRAM_D43") (class "Default")
      (node (ref "U7") (pin "A7") (pinfunction "DQ12_A7") (pintype "passive"))
    )
    (net (code "71") (name "/DRAM_D44") (class "Default")
      (node (ref "U7") (pin "A2") (pinfunction "DQ13_A2") (pintype "passive"))
    )
    (net (code "72") (name "/DRAM_D45") (class "Default")
      (node (ref "U7") (pin "C8") (pinfunction "DQ10_C8") (pintype "passive"))
    )
    (net (code "73") (name "/DRAM_D46") (class "Default")
      (node (ref "U7") (pin "A3") (pinfunction "DQ15_A3") (pintype "passive"))
    )
    (net (code "74") (name "/DRAM_D47") (class "Default")
      (node (ref "U7") (pin "C3") (pinfunction "DQ9_C3") (pintype "passive"))
    )
    (net (code "75") (name "/DRAM_D48") (class "Default")
      (node (ref "U5") (pin "D7") (pinfunction "DQ8_D7") (pintype "passive"))
    )
    (net (code "76") (name "/DRAM_D49") (class "Default")
      (node (ref "U5") (pin "C2") (pinfunction "DQ11_C2") (pintype "passive"))
    )
    (net (code "77") (name "/DRAM_D50") (class "Default")
      (node (ref "U5") (pin "C3") (pinfunction "DQ9_C3") (pintype "passive"))
    )
    (net (code "78") (name "/DRAM_D51") (class "Default")
      (node (ref "U5") (pin "B8") (pinfunction "DQ14_B8") (pintype "passive"))
    )
    (net (code "79") (name "/DRAM_D52") (class "Default")
      (node (ref "U5") (pin "A7") (pinfunction "DQ12_A7") (pintype "passive"))
    )
    (net (code "80") (name "/DRAM_D53") (class "Default")
      (node (ref "U5") (pin "C8") (pinfunction "DQ10_C8") (pintype "passive"))
    )
    (net (code "81") (name "/DRAM_D54") (class "Default")
      (node (ref "U5") (pin "A3") (pinfunction "DQ15_A3") (pintype "passive"))
    )
    (net (code "82") (name "/DRAM_D55") (class "Default")
      (node (ref "U5") (pin "A2") (pinfunction "DQ13_A2") (pintype "passive"))
    )
    (net (code "83") (name "/DRAM_D56") (class "Default")
      (node (ref "U5") (pin "E3") (pinfunction "DQ0_E3") (pintype "passive"))
    )
    (net (code "84") (name "/DRAM_D57") (class "Default")
      (node (ref "U5") (pin "G2") (pinfunction "DQ6_G2") (pintype "passive"))
    )
    (net (code "85") (name "/DRAM_D58") (class "Default")
      (node (ref "U5") (pin "H7") (pinfunction "DQ7_H7") (pintype "passive"))
    )
    (net (code "86") (name "/DRAM_D59") (class "Default")
      (node (ref "U5") (pin "F7") (pinfunction "DQ1_F7") (pintype "passive"))
    )
    (net (code "87") (name "/DRAM_D60") (class "Default")
      (node (ref "U5") (pin "H3") (pinfunction "DQ4_H3") (pintype "passive"))
    )
    (net (code "88") (name "/DRAM_D61") (class "Default")
      (node (ref "U5") (pin "F2") (pinfunction "DQ2_F2") (pintype "passive"))
    )
    (net (code "89") (name "/DRAM_D62") (class "Default")
      (node (ref "U5") (pin "F8") (pinfunction "DQ3_F8") (pintype "passive"))
    )
    (net (code "90") (name "/DRAM_D63") (class "Default")
      (node (ref "U5") (pin "H8") (pinfunction "DQ5_H8") (pintype "passive"))
    )
    (net (code "91") (name "/DRAM_DQM0") (class "Default")
      (node (ref "U4") (pin "D3") (pinfunction "UDM_D3") (pintype "passive"))
    )
    (net (code "92") (name "/DRAM_DQM1") (class "Default")
      (node (ref "U4") (pin "E7") (pinfunction "LDM_E7") (pintype "passive"))
    )
    (net (code "93") (name "/DRAM_DQM2") (class "Default")
      (node (ref "U6") (pin "E7") (pinfunction "LDM_E7") (pintype "passive"))
    )
    (net (code "94") (name "/DRAM_DQM3") (class "Default")
      (node (ref "U6") (pin "D3") (pinfunction "UDM_D3") (pintype "passive"))
    )
    (net (code "95") (name "/DRAM_DQM4") (class "Default")
      (node (ref "U7") (pin "E7") (pinfunction "LDM_E7") (pintype "passive"))
    )
    (net (code "96") (name "/DRAM_DQM5") (class "Default")
      (node (ref "U7") (pin "D3") (pinfunction "UDM_D3") (pintype "passive"))
    )
    (net (code "97") (name "/DRAM_DQM6") (class "Default")
      (node (ref "U5") (pin "D3") (pinfunction "UDM_D3") (pintype "passive"))
    )
    (net (code "98") (name "/DRAM_DQM7") (class "Default")
      (node (ref "U5") (pin "E7") (pinfunction "LDM_E7") (pintype "passive"))
    )
    (net (code "99") (name "/DRAM_DQS0_N") (class "Default")
      (node (ref "U4") (pin "B7") (pinfunction "~{UDQS}_B7") (pintype "passive"))
    )
    (net (code "100") (name "/DRAM_DQS0_P") (class "Default")
      (node (ref "U4") (pin "C7") (pinfunction "UDQS_C7") (pintype "passive"))
    )
    (net (code "101") (name "/DRAM_DQS1_N") (class "Default")
      (node (ref "U4") (pin "G3") (pinfunction "~{LDQS}_G3") (pintype "passive"))
    )
    (net (code "102") (name "/DRAM_DQS1_P") (class "Default")
      (node (ref "U4") (pin "F3") (pinfunction "LDQS_F3") (pintype "passive"))
    )
    (net (code "103") (name "/DRAM_DQS2_N") (class "Default")
      (node (ref "U6") (pin "G3") (pinfunction "~{LDQS}_G3") (pintype "passive"))
    )
    (net (code "104") (name "/DRAM_DQS2_P") (class "Default")
      (node (ref "U6") (pin "F3") (pinfunction "LDQS_F3") (pintype "passive"))
    )
    (net (code "105") (name "/DRAM_DQS3_N") (class "Default")
      (node (ref "U6") (pin "B7") (pinfunction "~{UDQS}_B7") (pintype "passive"))
    )
    (net (code "106") (name "/DRAM_DQS3_P") (class "Default")
      (node (ref "U6") (pin "C7") (pinfunction "UDQS_C7") (pintype "passive"))
    )
    (net (code "107") (name "/DRAM_DQS4_N") (class "Default")
      (node (ref "U7") (pin "G3") (pinfunction "~{LDQS}_G3") (pintype "passive"))
    )
    (net (code "108") (name "/DRAM_DQS4_P") (class "Default")
      (node (ref "U7") (pin "F3") (pinfunction "LDQS_F3") (pintype "passive"))
    )
    (net (code "109") (name "/DRAM_DQS5_N") (class "Default")
      (node (ref "U7") (pin "B7") (pinfunction "~{UDQS}_B7") (pintype "passive"))
    )
    (net (code "110") (name "/DRAM_DQS5_P") (class "Default")
      (node (ref "U7") (pin "C7") (pinfunction "UDQS_C7") (pintype "passive"))
    )
    (net (code "111") (name "/DRAM_DQS6_N") (class "Default")
      (node (ref "U5") (pin "B7") (pinfunction "~{UDQS}_B7") (pintype "passive"))
    )
    (net (code "112") (name "/DRAM_DQS6_P") (class "Default")
      (node (ref "U5") (pin "C7") (pinfunction "UDQS_C7") (pintype "passive"))
    )
    (net (code "113") (name "/DRAM_DQS7_N") (class "Default")
      (node (ref "U5") (pin "G3") (pinfunction "~{LDQS}_G3") (pintype "passive"))
    )
    (net (code "114") (name "/DRAM_DQS7_P") (class "Default")
      (node (ref "U5") (pin "F3") (pinfunction "LDQS_F3") (pintype "passive"))
    )
    (net (code "116") (name "/DRAM_RAS_B") (class "Default")
      (node (ref "U4") (pin "J3") (pinfunction "~{RAS}_J3") (pintype "passive"))
      (node (ref "U5") (pin "J3") (pinfunction "~{RAS}_J3") (pintype "passive"))
      (node (ref "U6") (pin "J3") (pinfunction "~{RAS}_J3") (pintype "passive"))
      (node (ref "U7") (pin "J3") (pinfunction "~{RAS}_J3") (pintype "passive"))
    )
    (net (code "117") (name "/DRAM_RESET_B") (class "Default")
      (node (ref "U4") (pin "T2") (pinfunction "~{RESET}_T2") (pintype "passive"))
      (node (ref "U5") (pin "T2") (pinfunction "~{RESET}_T2") (pintype "passive"))
      (node (ref "U6") (pin "T2") (pinfunction "~{RESET}_T2") (pintype "passive"))
      (node (ref "U7") (pin "T2") (pinfunction "~{RESET}_T2") (pintype "passive"))
    )
    (net (code "118") (name "/DRAM_SDBA0") (class "Default")
      (node (ref "U4") (pin "M2") (pinfunction "BA0_M2") (pintype "passive"))
      (node (ref "U5") (pin "M2") (pinfunction "BA0_M2") (pintype "passive"))
      (node (ref "U6") (pin "M2") (pinfunction "BA0_M2") (pintype "passive"))
      (node (ref "U7") (pin "M2") (pinfunction "BA0_M2") (pintype "passive"))
    )
    (net (code "119") (name "/DRAM_SDBA1") (class "Default")
      (node (ref "U4") (pin "N8") (pinfunction "BA1_N8") (pintype "passive"))
      (node (ref "U5") (pin "N8") (pinfunction "BA1_N8") (pintype "passive"))
      (node (ref "U6") (pin "N8") (pinfunction "BA1_N8") (pintype "passive"))
      (node (ref "U7") (pin "N8") (pinfunction "BA1_N8") (pintype "passive"))
    )
    (net (code "120") (name "/DRAM_SDBA2") (class "Default")
      (node (ref "U4") (pin "M3") (pinfunction "BA2_M3") (pintype "passive"))
      (node (ref "U5") (pin "M3") (pinfunction "BA2_M3") (pintype "passive"))
      (node (ref "U6") (pin "M3") (pinfunction "BA2_M3") (pintype "passive"))
      (node (ref "U7") (pin "M3") (pinfunction "BA2_M3") (pintype "passive"))
    )
    (net (code "121") (name "/DRAM_SDCKE0") (class "Default")
      (node (ref "U4") (pin "K9") (pinfunction "CKE_K9") (pintype "passive"))
      (node (ref "U5") (pin "K9") (pinfunction "CKE_K9") (pintype "passive"))
      (node (ref "U6") (pin "K9") (pinfunction "CKE_K9") (pintype "passive"))
      (node (ref "U7") (pin "K9") (pinfunction "CKE_K9") (pintype "passive"))
    )
    (net (code "122") (name "/DRAM_SDODT0") (class "Default")
      (node (ref "U4") (pin "K1") (pinfunction "ODT_K1") (pintype "passive"))
      (node (ref "U5") (pin "K1") (pinfunction "ODT_K1") (pintype "passive"))
      (node (ref "U6") (pin "K1") (pinfunction "ODT_K1") (pintype "passive"))
      (node (ref "U7") (pin "K1") (pinfunction "ODT_K1") (pintype "passive"))
    )
    (net (code "123") (name "/DRAM_WE_B") (class "Default")
      (node (ref "U4") (pin "L3") (pinfunction "~{WE}_L3") (pintype "passive"))
      (node (ref "U5") (pin "L3") (pinfunction "~{WE}_L3") (pintype "passive"))
      (node (ref "U6") (pin "L3") (pinfunction "~{WE}_L3") (pintype "passive"))
      (node (ref "U7") (pin "L3") (pinfunction "~{WE}_L3") (pintype "passive"))
    )
    (net (code "126") (name "GND") (class "Default")
      (node (ref "C42") (pin "1") (pinfunction "1_1") (pintype "passive"))
      (node (ref "C43") (pin "1") (pinfunction "1_1") (pintype "passive"))
      (node (ref "C44") (pin "1") (pinfunction "1_1") (pintype "passive"))
      (node (ref "C45") (pin "1") (pinfunction "1_1") (pintype "passive"))
      (node (ref "C46") (pin "2") (pinfunction "2_2") (pintype "passive"))
      (node (ref "C47") (pin "2") (pinfunction "2_2") (pintype "passive"))
      (node (ref "C48") (pin "2") (pinfunction "2_2") (pintype "passive"))
      (node (ref "C49") (pin "2") (pinfunction "2_2") (pintype "passive"))
      (node (ref "C50") (pin "2") (pinfunction "2_2") (pintype "passive"))
      (node (ref "C51") (pin "2") (pinfunction "2_2") (pintype "passive"))
      (node (ref "C52") (pin "2") (pinfunction "2_2") (pintype "passive"))
      (node (ref "C53") (pin "2") (pinfunction "2_2") (pintype "passive"))
      (node (ref "C54") (pin "2") (pinfunction "2_2") (pintype "passive"))
      (node (ref "C55") (pin "2") (pinfunction "2_2") (pintype "passive"))
      (node (ref "C56") (pin "2") (pinfunction "2_2") (pintype "passive"))
      (node (ref "C57") (pin "2") (pinfunction "2_2") (pintype "passive"))
      (node (ref "C58") (pin "2") (pinfunction "2_2") (pintype "passive"))
      (node (ref "C59") (pin "2") (pinfunction "2_2") (pintype "passive"))
      (node (ref "C60") (pin "2") (pinfunction "2_2") (pintype "passive"))
      (node (ref "C61") (pin "2") (pinfunction "2_2") (pintype "passive"))
      (node (ref "C62") (pin "2") (pinfunction "2_2") (pintype "passive"))
      (node (ref "C63") (pin "2") (pinfunction "2_2") (pintype "passive"))
      (node (ref "C64") (pin "2") (pinfunction "2_2") (pintype "passive"))
      (node (ref "C65") (pin "2") (pinfunction "2_2") (pintype "passive"))
      (node (ref "C66") (pin "2") (pinfunction "2_2") (pintype "passive"))
      (node (ref "C67") (pin "2") (pinfunction "2_2") (pintype "passive"))
      (node (ref "C68") (pin "2") (pinfunction "2_2") (pintype "passive"))
      (node (ref "C69") (pin "2") (pinfunction "2_2") (pintype "passive"))
      (node (ref "C70") (pin "2") (pinfunction "2_2") (pintype "passive"))
      (node (ref "C71") (pin "2") (pinfunction "2_2") (pintype "passive"))
      (node (ref "C72") (pin "1") (pinfunction "1_1") (pintype "passive"))
      (node (ref "C73") (pin "1") (pinfunction "1_1") (pintype "passive"))
      (node (ref "C74") (pin "1") (pinfunction "1_1") (pintype "passive"))
      (node (ref "C75") (pin "1") (pinfunction "1_1") (pintype "passive"))
      (node (ref "C76") (pin "2") (pinfunction "2_2") (pintype "passive"))
      (node (ref "C77") (pin "2") (pinfunction "2_2") (pintype "passive"))
      (node (ref "C78") (pin "2") (pinfunction "2_2") (pintype "passive"))
      (node (ref "C79") (pin "2") (pinfunction "2_2") (pintype "passive"))
      (node (ref "C80") (pin "2") (pinfunction "2_2") (pintype "passive"))
      (node (ref "C81") (pin "2") (pinfunction "2_2") (pintype "passive"))
      (node (ref "C82") (pin "2") (pinfunction "2_2") (pintype "passive"))
      (node (ref "C83") (pin "2") (pinfunction "2_2") (pintype "passive"))
      (node (ref "C84") (pin "2") (pinfunction "2_2") (pintype "passive"))
      (node (ref "C85") (pin "2") (pinfunction "2_2") (pintype "passive"))
      (node (ref "C86") (pin "2") (pinfunction "2_2") (pintype "passive"))
      (node (ref "C87") (pin "2") (pinfunction "2_2") (pintype "passive"))
      (node (ref "C88") (pin "2") (pinfunction "2_2") (pintype "passive"))
      (node (ref "C89") (pin "2") (pinfunction "2_2") (pintype "passive"))
      (node (ref "C90") (pin "2") (pinfunction "2_2") (pintype "passive"))
      (node (ref "R47") (pin "2") (pinfunction "2_2") (pintype "passive"))
      (node (ref "R48") (pin "2") (pinfunction "2_2") (pintype "passive"))
      (node (ref "R49") (pin "2") (pinfunction "2_2") (pintype "passive"))
      (node (ref "R50") (pin "2") (pinfunction "2_2") (pintype "passive"))
      (node (ref "U4") (pin "A9") (pinfunction "VSS1_A9") (pintype "passive"))
      (node (ref "U4") (pin "B1") (pinfunction "VSSQ1_B1") (pintype "passive"))
      (node (ref "U4") (pin "B3") (pinfunction "VSS2_B3") (pintype "passive"))
      (node (ref "U4") (pin "B9") (pinfunction "VSSQ2_B9") (pintype "passive"))
      (node (ref "U4") (pin "D1") (pinfunction "VSSQ3_D1") (pintype "passive"))
      (node (ref "U4") (pin "D8") (pinfunction "VSSQ4_D8") (pintype "passive"))
      (node (ref "U4") (pin "E1") (pinfunction "VSS3_E1") (pintype "passive"))
      (node (ref "U4") (pin "E2") (pinfunction "VSSQ5_E2") (pintype "passive"))
      (node (ref "U4") (pin "E8") (pinfunction "VSSQ6_E8") (pintype "passive"))
      (node (ref "U4") (pin "F9") (pinfunction "VSSQ7_F9") (pintype "passive"))
      (node (ref "U4") (pin "G1") (pinfunction "VSSQ8_G1") (pintype "passive"))
      (node (ref "U4") (pin "G8") (pinfunction "VSS4_G8") (pintype "passive"))
      (node (ref "U4") (pin "G9") (pinfunction "VSSQ9_G9") (pintype "passive"))
      (node (ref "U4") (pin "J2") (pinfunction "VSS5_J2") (pintype "passive"))
      (node (ref "U4") (pin "J8") (pinfunction "VSS6_J8") (pintype "passive"))
      (node (ref "U4") (pin "M1") (pinfunction "VSS7_M1") (pintype "passive"))
      (node (ref "U4") (pin "M9") (pinfunction "VSS8_M9") (pintype "passive"))
      (node (ref "U4") (pin "P1") (pinfunction "VSS9_P1") (pintype "passive"))
      (node (ref "U4") (pin "P9") (pinfunction "VSS10_P9") (pintype "passive"))
      (node (ref "U4") (pin "T1") (pinfunction "VSS11_T1") (pintype "passive"))
      (node (ref "U4") (pin "T9") (pinfunction "VSS12_T9") (pintype "passive"))
      (node (ref "U5") (pin "A9") (pinfunction "VSS1_A9") (pintype "passive"))
      (node (ref "U5") (pin "B1") (pinfunction "VSSQ1_B1") (pintype "passive"))
      (node (ref "U5") (pin "B3") (pinfunction "VSS2_B3") (pintype "passive"))
      (node (ref "U5") (pin "B9") (pinfunction "VSSQ2_B9") (pintype "passive"))
      (node (ref "U5") (pin "D1") (pinfunction "VSSQ3_D1") (pintype "passive"))
      (node (ref "U5") (pin "D8") (pinfunction "VSSQ4_D8") (pintype "passive"))
      (node (ref "U5") (pin "E1") (pinfunction "VSS3_E1") (pintype "passive"))
      (node (ref "U5") (pin "E2") (pinfunction "VSSQ5_E2") (pintype "passive"))
      (node (ref "U5") (pin "E8") (pinfunction "VSSQ6_E8") (pintype "passive"))
      (node (ref "U5") (pin "F9") (pinfunction "VSSQ7_F9") (pintype "passive"))
      (node (ref "U5") (pin "G1") (pinfunction "VSSQ8_G1") (pintype "passive"))
      (node (ref "U5") (pin "G8") (pinfunction "VSS4_G8") (pintype "passive"))
      (node (ref "U5") (pin "G9") (pinfunction "VSSQ9_G9") (pintype "passive"))
      (node (ref "U5") (pin "J2") (pinfunction "VSS5_J2") (pintype "passive"))
      (node (ref "U5") (pin "J8") (pinfunction "VSS6_J8") (pintype "passive"))
      (node (ref "U5") (pin "M1") (pinfunction "VSS7_M1") (pintype "passive"))
      (node (ref "U5") (pin "M9") (pinfunction "VSS8_M9") (pintype "passive"))
      (node (ref "U5") (pin "P1") (pinfunction "VSS9_P1") (pintype "passive"))
      (node (ref "U5") (pin "P9") (pinfunction "VSS10_P9") (pintype "passive"))
      (node (ref "U5") (pin "T1") (pinfunction "VSS11_T1") (pintype "passive"))
      (node (ref "U5") (pin "T9") (pinfunction "VSS12_T9") (pintype "passive"))
      (node (ref "U6") (pin "A9") (pinfunction "VSS1_A9") (pintype "passive"))
      (node (ref "U6") (pin "B1") (pinfunction "VSSQ1_B1") (pintype "passive"))
      (node (ref "U6") (pin "B3") (pinfunction "VSS2_B3") (pintype "passive"))
      (node (ref "U6") (pin "B9") (pinfunction "VSSQ2_B9") (pintype "passive"))
      (node (ref "U6") (pin "D1") (pinfunction "VSSQ3_D1") (pintype "passive"))
      (node (ref "U6") (pin "D8") (pinfunction "VSSQ4_D8") (pintype "passive"))
      (node (ref "U6") (pin "E1") (pinfunction "VSS3_E1") (pintype "passive"))
      (node (ref "U6") (pin "E2") (pinfunction "VSSQ5_E2") (pintype "passive"))
      (node (ref "U6") (pin "E8") (pinfunction "VSSQ6_E8") (pintype "passive"))
      (node (ref "U6") (pin "F9") (pinfunction "VSSQ7_F9") (pintype "passive"))
      (node (ref "U6") (pin "G1") (pinfunction "VSSQ8_G1") (pintype "passive"))
      (node (ref "U6") (pin "G8") (pinfunction "VSS4_G8") (pintype "passive"))
      (node (ref "U6") (pin "G9") (pinfunction "VSSQ9_G9") (pintype "passive"))
      (node (ref "U6") (pin "J2") (pinfunction "VSS5_J2") (pintype "passive"))
      (node (ref "U6") (pin "J8") (pinfunction "VSS6_J8") (pintype "passive"))
      (node (ref "U6") (pin "M1") (pinfunction "VSS7_M1") (pintype "passive"))
      (node (ref "U6") (pin "M9") (pinfunction "VSS8_M9") (pintype "passive"))
      (node (ref "U6") (pin "P1") (pinfunction "VSS9_P1") (pintype "passive"))
      (node (ref "U6") (pin "P9") (pinfunction "VSS10_P9") (pintype "passive"))
      (node (ref "U6") (pin "T1") (pinfunction "VSS11_T1") (pintype "passive"))
      (node (ref "U6") (pin "T9") (pinfunction "VSS12_T9") (pintype "passive"))
      (node (ref "U7") (pin "A9") (pinfunction "VSS1_A9") (pintype "passive"))
      (node (ref "U7") (pin "B1") (pinfunction "VSSQ1_B1") (pintype "passive"))
      (node (ref "U7") (pin "B3") (pinfunction "VSS2_B3") (pintype "passive"))
      (node (ref "U7") (pin "B9") (pinfunction "VSSQ2_B9") (pintype "passive"))
      (node (ref "U7") (pin "D1") (pinfunction "VSSQ3_D1") (pintype "passive"))
      (node (ref "U7") (pin "D8") (pinfunction "VSSQ4_D8") (pintype "passive"))
      (node (ref "U7") (pin "E1") (pinfunction "VSS3_E1") (pintype "passive"))
      (node (ref "U7") (pin "E2") (pinfunction "VSSQ5_E2") (pintype "passive"))
      (node (ref "U7") (pin "E8") (pinfunction "VSSQ6_E8") (pintype "passive"))
      (node (ref "U7") (pin "F9") (pinfunction "VSSQ7_F9") (pintype "passive"))
      (node (ref "U7") (pin "G1") (pinfunction "VSSQ8_G1") (pintype "passive"))
      (node (ref "U7") (pin "G8") (pinfunction "VSS4_G8") (pintype "passive"))
      (node (ref "U7") (pin "G9") (pinfunction "VSSQ9_G9") (pintype "passive"))
      (node (ref "U7") (pin "J2") (pinfunction "VSS5_J2") (pintype "passive"))
      (node (ref "U7") (pin "J8") (pinfunction "VSS6_J8") (pintype "passive"))
      (node (ref "U7") (pin "M1") (pinfunction "VSS7_M1") (pintype "passive"))
      (node (ref "U7") (pin "M9") (pinfunction "VSS8_M9") (pintype "passive"))
      (node (ref "U7") (pin "P1") (pinfunction "VSS9_P1") (pintype "passive"))
      (node (ref "U7") (pin "P9") (pinfunction "VSS10_P9") (pintype "passive"))
      (node (ref "U7") (pin "T1") (pinfunction "VSS11_T1") (pintype "passive"))
      (node (ref "U7") (pin "T9") (pinfunction "VSS12_T9") (pintype "passive"))
    )
    (net (code "127") (name "Net-(U4-ZQ)") (class "Default")
      (node (ref "R47") (pin "1") (pinfunction "1_1") (pintype "passive"))
      (node (ref "U4") (pin "L8") (pinfunction "ZQ_L8") (pintype "passive"))
    )
    (net (code "128") (name "Net-(U5-ZQ)") (class "Default")
      (node (ref "R48") (pin "1") (pinfunction "1_1") (pintype "passive"))
      (node (ref "U5") (pin "L8") (pinfunction "ZQ_L8") (pintype "passive"))
    )
    (net (code "129") (name "Net-(U6-ZQ)") (class "Default")
      (node (ref "R49") (pin "1") (pinfunction "1_1") (pintype "passive"))
      (node (ref "U6") (pin "L8") (pinfunction "ZQ_L8") (pintype "passive"))
    )
    (net (code "130") (name "Net-(U7-ZQ)") (class "Default")
      (node (ref "R50") (pin "1") (pinfunction "1_1") (pintype "passive"))
      (node (ref "U7") (pin "L8") (pinfunction "ZQ_L8") (pintype "passive"))
    )
    (net (code "131") (name "unconnected-(U4-NC_J1-PadJ1)") (class "Default")
      (node (ref "U4") (pin "J1") (pinfunction "NC_J1_J1") (pintype "passive+no_connect"))
    )
    (net (code "132") (name "unconnected-(U4-NC_J9-PadJ9)") (class "Default")
      (node (ref "U4") (pin "J9") (pinfunction "NC_J9_J9") (pintype "passive+no_connect"))
    )
    (net (code "133") (name "unconnected-(U4-NC_L1-PadL1)") (class "Default")
      (node (ref "U4") (pin "L1") (pinfunction "NC_L1_L1") (pintype "passive+no_connect"))
    )
    (net (code "134") (name "unconnected-(U4-NC_L9-PadL9)") (class "Default")
      (node (ref "U4") (pin "L9") (pinfunction "NC_L9_L9") (pintype "passive+no_connect"))
    )
    (net (code "135") (name "unconnected-(U5-NC_J1-PadJ1)") (class "Default")
      (node (ref "U5") (pin "J1") (pinfunction "NC_J1_J1") (pintype "passive+no_connect"))
    )
    (net (code "136") (name "unconnected-(U5-NC_J9-PadJ9)") (class "Default")
      (node (ref "U5") (pin "J9") (pinfunction "NC_J9_J9") (pintype "passive+no_connect"))
    )
    (net (code "137") (name "unconnected-(U5-NC_L1-PadL1)") (class "Default")
      (node (ref "U5") (pin "L1") (pinfunction "NC_L1_L1") (pintype "passive+no_connect"))
    )
    (net (code "138") (name "unconnected-(U5-NC_L9-PadL9)") (class "Default")
      (node (ref "U5") (pin "L9") (pinfunction "NC_L9_L9") (pintype "passive+no_connect"))
    )
    (net (code "139") (name "unconnected-(U6-NC_J1-PadJ1)") (class "Default")
      (node (ref "U6") (pin "J1") (pinfunction "NC_J1_J1") (pintype "passive+no_connect"))
    )
    (net (code "140") (name "unconnected-(U6-NC_J9-PadJ9)") (class "Default")
      (node (ref "U6") (pin "J9") (pinfunction "NC_J9_J9") (pintype "passive+no_connect"))
    )
    (net (code "141") (name "unconnected-(U6-NC_L1-PadL1)") (class "Default")
      (node (ref "U6") (pin "L1") (pinfunction "NC_L1_L1") (pintype "passive+no_connect"))
    )
    (net (code "142") (name "unconnected-(U6-NC_L9-PadL9)") (class "Default")
      (node (ref "U6") (pin "L9") (pinfunction "NC_L9_L9") (pintype "passive+no_connect"))
    )
    (net (code "143") (name "unconnected-(U7-NC_J1-PadJ1)") (class "Default")
      (node (ref "U7") (pin "J1") (pinfunction "NC_J1_J1") (pintype "passive+no_connect"))
    )
    (net (code "144") (name "unconnected-(U7-NC_J9-PadJ9)") (class "Default")
      (node (ref "U7") (pin "J9") (pinfunction "NC_J9_J9") (pintype "passive+no_connect"))
    )
    (net (code "145") (name "unconnected-(U7-NC_L1-PadL1)") (class "Default")
      (node (ref "U7") (pin "L1") (pinfunction "NC_L1_L1") (pintype "passive+no_connect"))
    )
    (net (code "146") (name "unconnected-(U7-NC_L9-PadL9)") (class "Default")
      (node (ref "U7") (pin "L9") (pinfunction "NC_L9_L9") (pintype "passive+no_connect"))
    )
  )
)
